# connector.net
KiCad netlist of a schematic drawn in Altium Designer
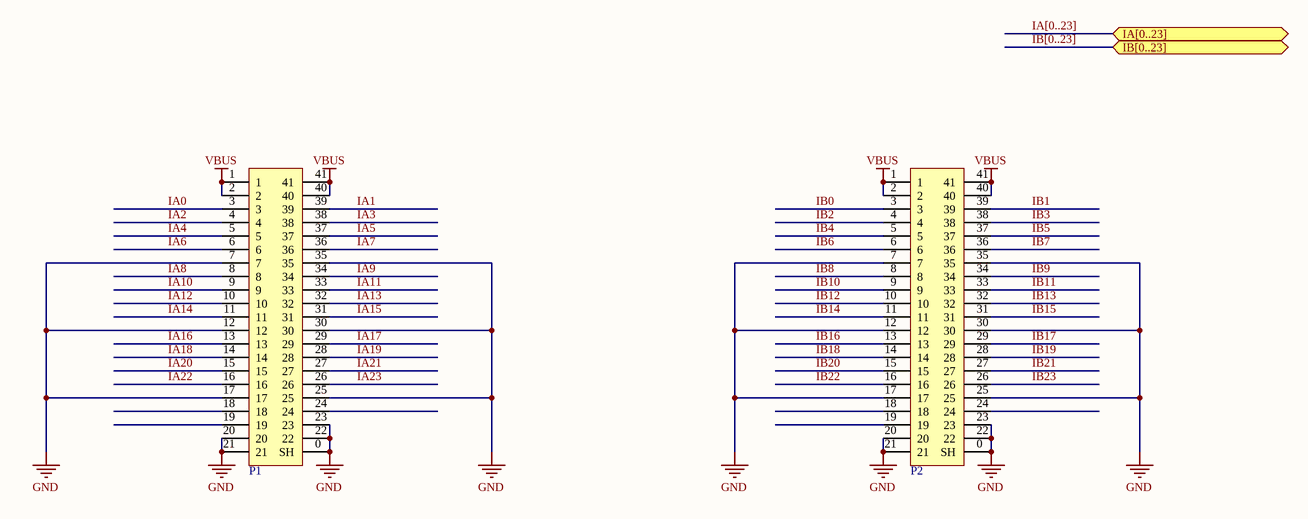
[diagram p0: connector.SchDoc]

(export (version "E")
  (design (tool "Eeschema 10.0.6"))
  (components
    (comp (ref "P1") (value "DF9-41S") (footprint "DF9-41S") (libsource (lib "cyusb3014") (part "DF9-41S")))
    (comp (ref "P2") (value "DF9-41S") (footprint "DF9-41S") (libsource (lib "cyusb3014") (part "DF9-41S")))
  )
  (nets
    (net (code "1") (name "/IA0") (class "Default")
      (node (ref "P1") (pin "3") (pinfunction "3_3") (pintype "passive"))
    )
    (net (code "2") (name "/IA1") (class "Default")
      (node (ref "P1") (pin "39") (pinfunction "39_39") (pintype "passive"))
    )
    (net (code "3") (name "/IA2") (class "Default")
      (node (ref "P1") (pin "4") (pinfunction "4_4") (pintype "passive"))
    )
    (net (code "4") (name "/IA3") (class "Default")
      (node (ref "P1") (pin "38") (pinfunction "38_38") (pintype "passive"))
    )
    (net (code "5") (name "/IA4") (class "Default")
      (node (ref "P1") (pin "5") (pinfunction "5_5") (pintype "passive"))
    )
    (net (code "6") (name "/IA5") (class "Default")
      (node (ref "P1") (pin "37") (pinfunction "37_37") (pintype "passive"))
    )
    (net (code "7") (name "/IA6") (class "Default")
      (node (ref "P1") (pin "6") (pinfunction "6_6") (pintype "passive"))
    )
    (net (code "8") (name "/IA7") (class "Default")
      (node (ref "P1") (pin "36") (pinfunction "36_36") (pintype "passive"))
    )
    (net (code "9") (name "/IA8") (class "Default")
      (node (ref "P1") (pin "8") (pinfunction "8_8") (pintype "passive"))
    )
    (net (code "10") (name "/IA9") (class "Default")
      (node (ref "P1") (pin "34") (pinfunction "34_34") (pintype "passive"))
    )
    (net (code "11") (name "/IA10") (class "Default")
      (node (ref "P1") (pin "9") (pinfunction "9_9") (pintype "passive"))
    )
    (net (code "12") (name "/IA11") (class "Default")
      (node (ref "P1") (pin "33") (pinfunction "33_33") (pintype "passive"))
    )
    (net (code "13") (name "/IA12") (class "Default")
      (node (ref "P1") (pin "10") (pinfunction "10_10") (pintype "passive"))
    )
    (net (code "14") (name "/IA13") (class "Default")
      (node (ref "P1") (pin "32") (pinfunction "32_32") (pintype "passive"))
    )
    (net (code "15") (name "/IA14") (class "Default")
      (node (ref "P1") (pin "11") (pinfunction "11_11") (pintype "passive"))
    )
    (net (code "16") (name "/IA15") (class "Default")
      (node (ref "P1") (pin "31") (pinfunction "31_31") (pintype "passive"))
    )
    (net (code "17") (name "/IA16") (class "Default")
      (node (ref "P1") (pin "13") (pinfunction "13_13") (pintype "passive"))
    )
    (net (code "18") (name "/IA17") (class "Default")
      (node (ref "P1") (pin "29") (pinfunction "29_29") (pintype "passive"))
    )
    (net (code "19") (name "/IA18") (class "Default")
      (node (ref "P1") (pin "14") (pinfunction "14_14") (pintype "passive"))
    )
    (net (code "20") (name "/IA19") (class "Default")
      (node (ref "P1") (pin "28") (pinfunction "28_28") (pintype "passive"))
    )
    (net (code "21") (name "/IA20") (class "Default")
      (node (ref "P1") (pin "15") (pinfunction "15_15") (pintype "passive"))
    )
    (net (code "22") (name "/IA21") (class "Default")
      (node (ref "P1") (pin "27") (pinfunction "27_27") (pintype "passive"))
    )
    (net (code "23") (name "/IA22") (class "Default")
      (node (ref "P1") (pin "16") (pinfunction "16_16") (pintype "passive"))
    )
    (net (code "24") (name "/IA23") (class "Default")
      (node (ref "P1") (pin "26") (pinfunction "26_26") (pintype "passive"))
    )
    (net (code "26") (name "/IB0") (class "Default")
      (node (ref "P2") (pin "3") (pinfunction "3_3") (pintype "passive"))
    )
    (net (code "27") (name "/IB1") (class "Default")
      (node (ref "P2") (pin "39") (pinfunction "39_39") (pintype "passive"))
    )
    (net (code "28") (name "/IB2") (class "Default")
      (node (ref "P2") (pin "4") (pinfunction "4_4") (pintype "passive"))
    )
    (net (code "29") (name "/IB3") (class "Default")
      (node (ref "P2") (pin "38") (pinfunction "38_38") (pintype "passive"))
    )
    (net (code "30") (name "/IB4") (class "Default")
      (node (ref "P2") (pin "5") (pinfunction "5_5") (pintype "passive"))
    )
    (net (code "31") (name "/IB5") (class "Default")
      (node (ref "P2") (pin "37") (pinfunction "37_37") (pintype "passive"))
    )
    (net (code "32") (name "/IB6") (class "Default")
      (node (ref "P2") (pin "6") (pinfunction "6_6") (pintype "passive"))
    )
    (net (code "33") (name "/IB7") (class "Default")
      (node (ref "P2") (pin "36") (pinfunction "36_36") (pintype "passive"))
    )
    (net (code "34") (name "/IB8") (class "Default")
      (node (ref "P2") (pin "8") (pinfunction "8_8") (pintype "passive"))
    )
    (net (code "35") (name "/IB9") (class "Default")
      (node (ref "P2") (pin "34") (pinfunction "34_34") (pintype "passive"))
    )
    (net (code "36") (name "/IB10") (class "Default")
      (node (ref "P2") (pin "9") (pinfunction "9_9") (pintype "passive"))
    )
    (net (code "37") (name "/IB11") (class "Default")
      (node (ref "P2") (pin "33") (pinfunction "33_33") (pintype "passive"))
    )
    (net (code "38") (name "/IB12") (class "Default")
      (node (ref "P2") (pin "10") (pinfunction "10_10") (pintype "passive"))
    )
    (net (code "39") (name "/IB13") (class "Default")
      (node (ref "P2") (pin "32") (pinfunction "32_32") (pintype "passive"))
    )
    (net (code "40") (name "/IB14") (class "Default")
      (node (ref "P2") (pin "11") (pinfunction "11_11") (pintype "passive"))
    )
    (net (code "41") (name "/IB15") (class "Default")
      (node (ref "P2") (pin "31") (pinfunction "31_31") (pintype "passive"))
    )
    (net (code "42") (name "/IB16") (class "Default")
      (node (ref "P2") (pin "13") (pinfunction "13_13") (pintype "passive"))
    )
    (net (code "43") (name "/IB17") (class "Default")
      (node (ref "P2") (pin "29") (pinfunction "29_29") (pintype "passive"))
    )
    (net (code "44") (name "/IB18") (class "Default")
      (node (ref "P2") (pin "14") (pinfunction "14_14") (pintype "passive"))
    )
    (net (code "45") (name "/IB19") (class "Default")
      (node (ref "P2") (pin "28") (pinfunction "28_28") (pintype "passive"))
    )
    (net (code "46") (name "/IB20") (class "Default")
      (node (ref "P2") (pin "15") (pinfunction "15_15") (pintype "passive"))
    )
    (net (code "47") (name "/IB21") (class "Default")
      (node (ref "P2") (pin "27") (pinfunction "27_27") (pintype "passive"))
    )
    (net (code "48") (name "/IB22") (class "Default")
      (node (ref "P2") (pin "16") (pinfunction "16_16") (pintype "passive"))
    )
    (net (code "49") (name "/IB23") (class "Default")
      (node (ref "P2") (pin "26") (pinfunction "26_26") (pintype "passive"))
    )
    (net (code "51") (name "GND") (class "Default")
      (node (ref "P1") (pin "0") (pinfunction "SH_0") (pintype "passive"))
      (node (ref "P1") (pin "12") (pinfunction "12_12") (pintype "passive"))
      (node (ref "P1") (pin "17") (pinfunction "17_17") (pintype "passive"))
      (node (ref "P1") (pin "20") (pinfunction "20_20") (pintype "passive"))
      (node (ref "P1") (pin "21") (pinfunction "21_21") (pintype "passive"))
      (node (ref "P1") (pin "22") (pinfunction "22_22") (pintype "passive"))
      (node (ref "P1") (pin "23") (pinfunction "23_23") (pintype "passive"))
      (node (ref "P1") (pin "25") (pinfunction "25_25") (pintype "passive"))
      (node (ref "P1") (pin "30") (pinfunction "30_30") (pintype "passive"))
      (node (ref "P1") (pin "35") (pinfunction "35_35") (pintype "passive"))
      (node (ref "P1") (pin "7") (pinfunction "7_7") (pintype "passive"))
      (node (ref "P2") (pin "0") (pinfunction "SH_0") (pintype "passive"))
      (node (ref "P2") (pin "12") (pinfunction "12_12") (pintype "passive"))
      (node (ref "P2") (pin "17") (pinfunction "17_17") (pintype "passive"))
      (node (ref "P2") (pin "20") (pinfunction "20_20") (pintype "passive"))
      (node (ref "P2") (pin "21") (pinfunction "21_21") (pintype "passive"))
      (node (ref "P2") (pin "22") (pinfunction "22_22") (pintype "passive"))
      (node (ref "P2") (pin "23") (pinfunction "23_23") (pintype "passive"))
      (node (ref "P2") (pin "25") (pinfunction "25_25") (pintype "passive"))
      (node (ref "P2") (pin "30") (pinfunction "30_30") (pintype "passive"))
      (node (ref "P2") (pin "35") (pinfunction "35_35") (pintype "passive"))
      (node (ref "P2") (pin "7") (pinfunction "7_7") (pintype "passive"))
    )
    (net (code "52") (name "VBUS") (class "Default")
      (node (ref "P1") (pin "1") (pinfunction "1_1") (pintype "passive"))
      (node (ref "P1") (pin "2") (pinfunction "2_2") (pintype "passive"))
      (node (ref "P1") (pin "40") (pinfunction "40_40") (pintype "passive"))
      (node (ref "P1") (pin "41") (pinfunction "41_41") (pintype "passive"))
      (node (ref "P2") (pin "1") (pinfunction "1_1") (pintype "passive"))
      (node (ref "P2") (pin "2") (pinfunction "2_2") (pintype "passive"))
      (node (ref "P2") (pin "40") (pinfunction "40_40") (pintype "passive"))
      (node (ref "P2") (pin "41") (pinfunction "41_41") (pintype "passive"))
    )
    (net (code "53") (name "unconnected-(P1-Pad18)") (class "Default")
      (node (ref "P1") (pin "18") (pinfunction "18_18") (pintype "passive"))
    )
    (net (code "54") (name "unconnected-(P1-Pad19)") (class "Default")
      (node (ref "P1") (pin "19") (pinfunction "19_19") (pintype "passive"))
    )
    (net (code "55") (name "unconnected-(P1-Pad24)") (class "Default")
      (node (ref "P1") (pin "24") (pinfunction "24_24") (pintype "passive"))
    )
    (net (code "56") (name "unconnected-(P2-Pad18)") (class "Default")
      (node (ref "P2") (pin "18") (pinfunction "18_18") (pintype "passive"))
    )
    (net (code "57") (name "unconnected-(P2-Pad19)") (class "Default")
      (node (ref "P2") (pin "19") (pinfunction "19_19") (pintype "passive"))
    )
    (net (code "58") (name "unconnected-(P2-Pad24)") (class "Default")
      (node (ref "P2") (pin "24") (pinfunction "24_24") (pintype "passive"))
    )
  )
)
